# CCM_0020_receiver.net
KiCad netlist of a schematic drawn in EAGLE
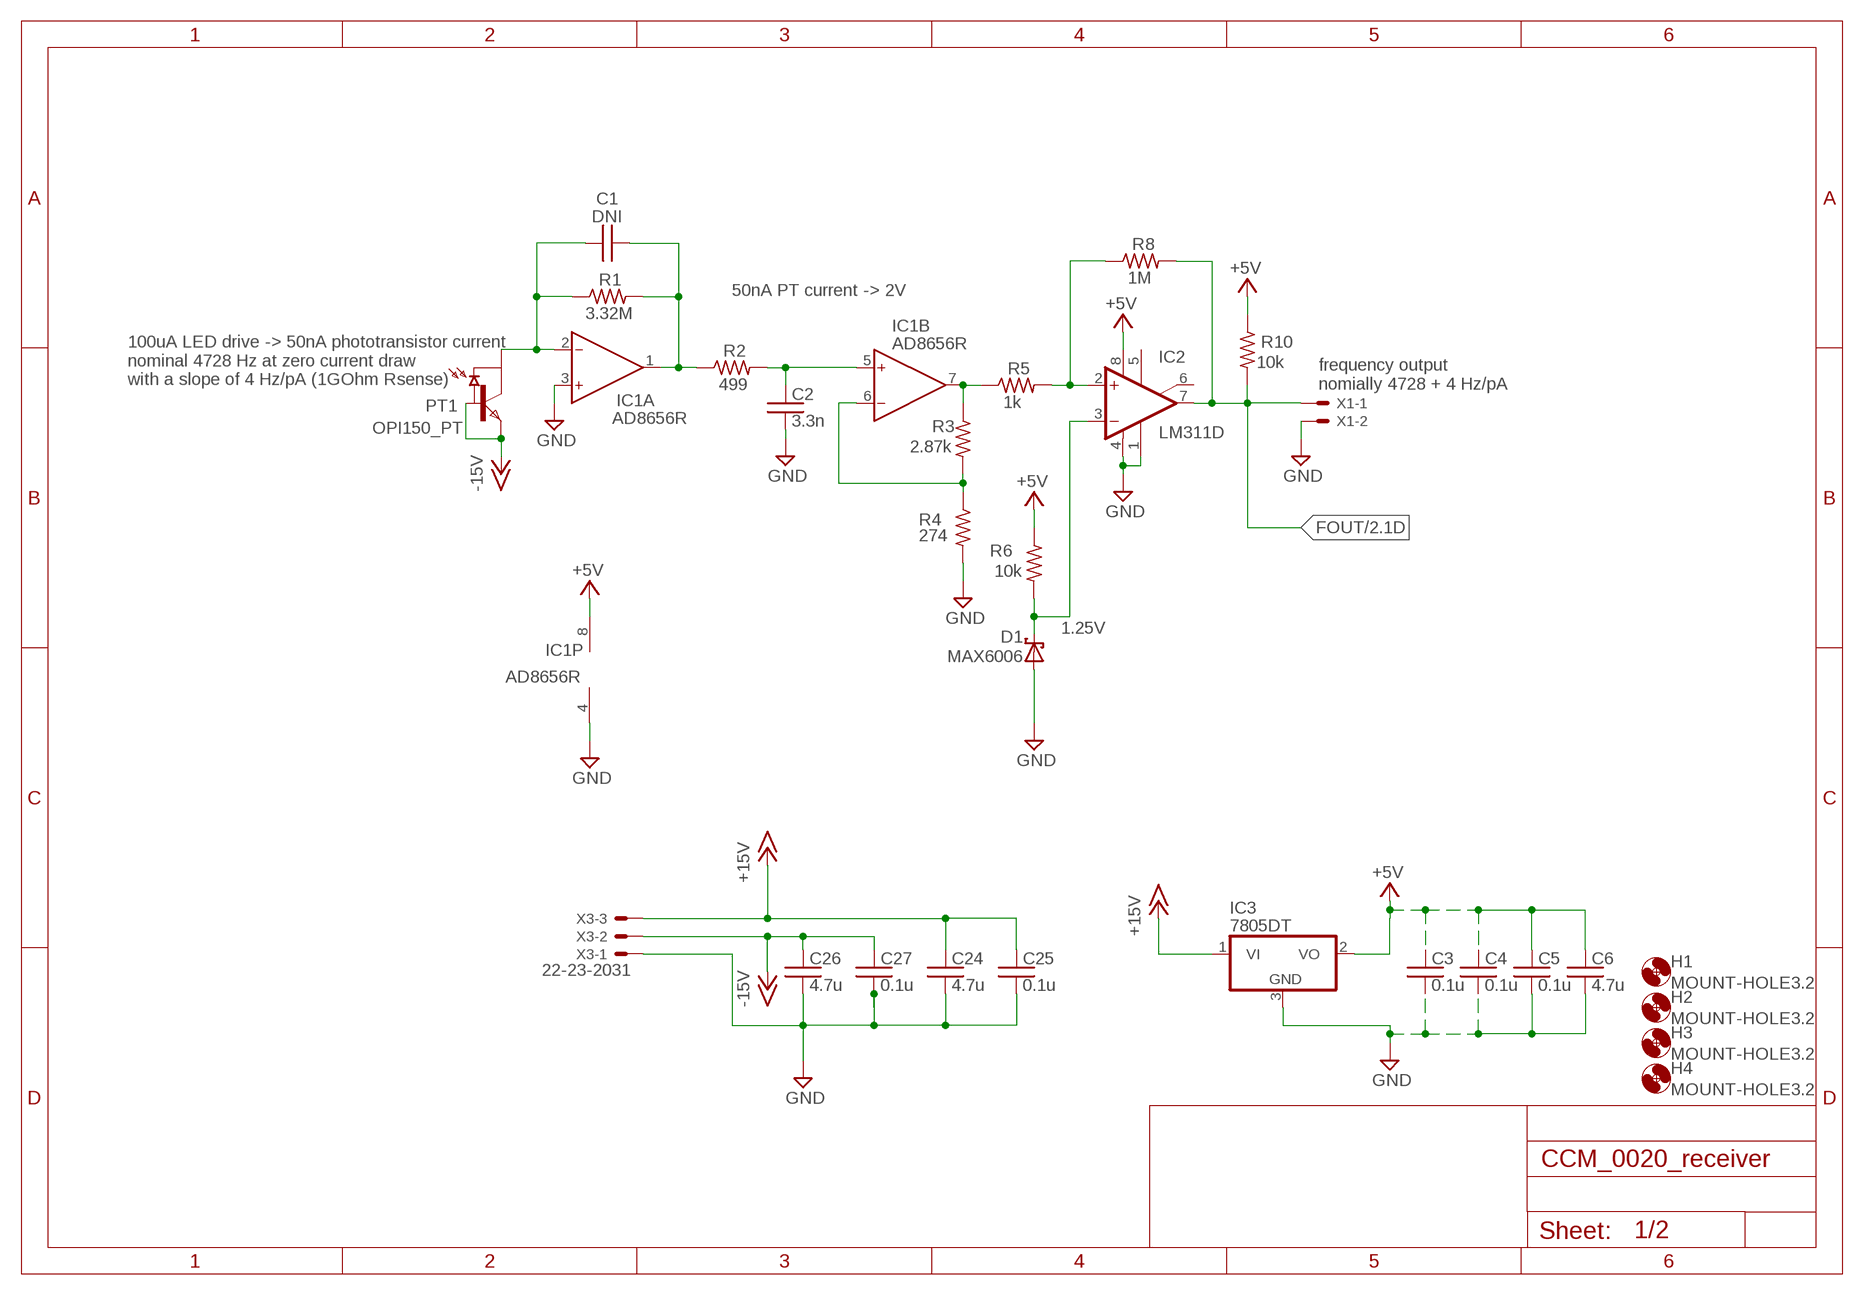
[diagram p0: schematic, sheet 1]
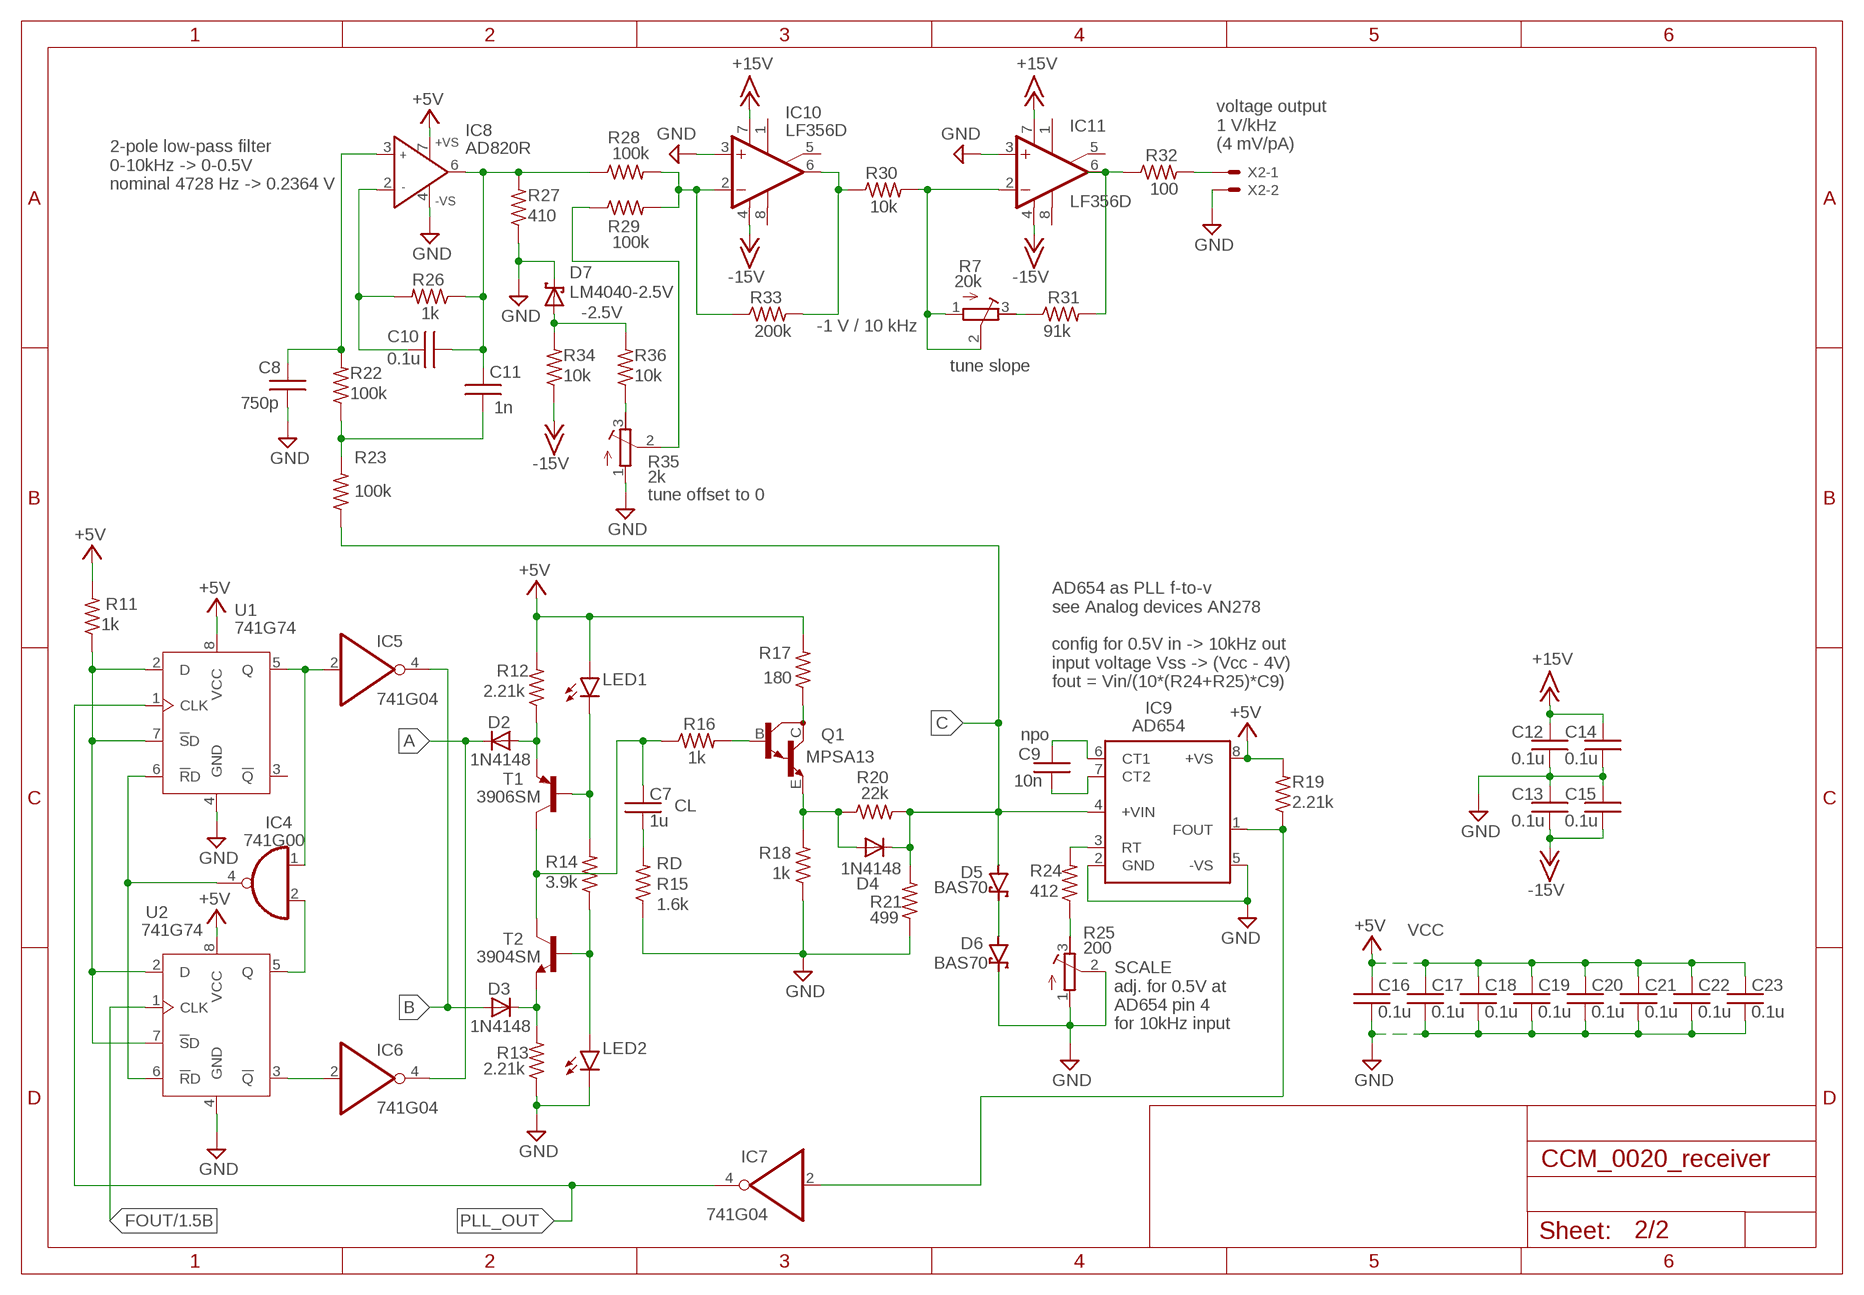
[diagram p1: schematic, sheet 2]

(export (version "E")
  (design (tool "Eeschema 10.0.6"))
  (components
    (comp (ref "C7")
      (value "1u")
      (footprint "eagle-import:0603")
      (libsource (lib "eagle-import") (part "C0603"))
    )
    (comp (ref "C8")
      (value "750p")
      (footprint "eagle-import:0603")
      (libsource (lib "eagle-import") (part "C0603"))
    )
    (comp (ref "C9")
      (value "10n")
      (footprint "eagle-import:0603")
      (libsource (lib "eagle-import") (part "C0603"))
    )
    (comp (ref "C10")
      (value "0.1u")
      (footprint "eagle-import:0603")
      (libsource (lib "eagle-import") (part "C0603"))
    )
    (comp (ref "C11")
      (value "1n")
      (footprint "eagle-import:0603")
      (libsource (lib "eagle-import") (part "C0603"))
    )
    (comp (ref "C12")
      (value "0.1u")
      (footprint "eagle-import:0603")
      (libsource (lib "eagle-import") (part "C0603"))
    )
    (comp (ref "C13")
      (value "0.1u")
      (footprint "eagle-import:0603")
      (libsource (lib "eagle-import") (part "C0603"))
    )
    (comp (ref "C14")
      (value "0.1u")
      (footprint "eagle-import:0603")
      (libsource (lib "eagle-import") (part "C0603"))
    )
    (comp (ref "C15")
      (value "0.1u")
      (footprint "eagle-import:0603")
      (libsource (lib "eagle-import") (part "C0603"))
    )
    (comp (ref "C16")
      (value "0.1u")
      (footprint "eagle-import:0603")
      (libsource (lib "eagle-import") (part "C0603"))
    )
    (comp (ref "C17")
      (value "0.1u")
      (footprint "eagle-import:0603")
      (libsource (lib "eagle-import") (part "C0603"))
    )
    (comp (ref "C18")
      (value "0.1u")
      (footprint "eagle-import:0603")
      (libsource (lib "eagle-import") (part "C0603"))
    )
    (comp (ref "C19")
      (value "0.1u")
      (footprint "eagle-import:0603")
      (libsource (lib "eagle-import") (part "C0603"))
    )
    (comp (ref "C20")
      (value "0.1u")
      (footprint "eagle-import:0603")
      (libsource (lib "eagle-import") (part "C0603"))
    )
    (comp (ref "C21")
      (value "0.1u")
      (footprint "eagle-import:0603")
      (libsource (lib "eagle-import") (part "C0603"))
    )
    (comp (ref "C22")
      (value "0.1u")
      (footprint "eagle-import:0603")
      (libsource (lib "eagle-import") (part "C0603"))
    )
    (comp (ref "C23")
      (value "0.1u")
      (footprint "eagle-import:0603")
      (libsource (lib "eagle-import") (part "C0603"))
    )
    (comp (ref "D2")
      (value "1N4148")
      (footprint "eagle-import:SOD323_ST")
      (libsource (lib "eagle-import") (part "1N4148"))
    )
    (comp (ref "D3")
      (value "1N4148")
      (footprint "eagle-import:SOD323_ST")
      (libsource (lib "eagle-import") (part "1N4148"))
    )
    (comp (ref "D4")
      (value "1N4148")
      (footprint "eagle-import:SOD323_ST")
      (libsource (lib "eagle-import") (part "1N4148"))
    )
    (comp (ref "D5")
      (value "BAS70")
      (footprint "eagle-import:SOT23")
      (libsource (lib "eagle-import") (part "BAS70"))
    )
    (comp (ref "D6")
      (value "BAS70")
      (footprint "eagle-import:SOT23")
      (libsource (lib "eagle-import") (part "BAS70"))
    )
    (comp (ref "D7")
      (value "LM4040-2.5V")
      (footprint "eagle-import:SOT23")
      (libsource (lib "eagle-import") (part "LM4040"))
    )
    (comp (ref "IC4")
      (value "741G00")
      (footprint "eagle-import:SOT23-5")
      (libsource (lib "eagle-import") (part "741G00DBVAHC"))
    )
    (comp (ref "IC5")
      (value "741G04")
      (footprint "eagle-import:SOT23-5")
      (libsource (lib "eagle-import") (part "741G04DBVAHC"))
    )
    (comp (ref "IC6")
      (value "741G04")
      (footprint "eagle-import:SOT23-5")
      (libsource (lib "eagle-import") (part "741G04DBVAHC"))
    )
    (comp (ref "IC7")
      (value "741G04")
      (footprint "eagle-import:SOT23-5")
      (libsource (lib "eagle-import") (part "741G04DBVAHC"))
    )
    (comp (ref "IC8")
      (value "AD820R")
      (footprint "eagle-import:SO8")
      (libsource (lib "eagle-import") (part "AD820R"))
    )
    (comp (ref "IC9")
      (value "AD654")
      (footprint "eagle-import:SO08")
      (libsource (lib "eagle-import") (part "AD654"))
    )
    (comp (ref "IC10")
      (value "LF356D")
      (footprint "eagle-import:SO08")
      (libsource (lib "eagle-import") (part "LF356D"))
    )
    (comp (ref "IC11")
      (value "LF356D")
      (footprint "eagle-import:SO08")
      (libsource (lib "eagle-import") (part "LF356D"))
    )
    (comp (ref "LED1")
      (value "LEDCHIP-LED0603")
      (footprint "eagle-import:CHIP-LED0603")
      (libsource (lib "eagle-import") (part "LEDCHIP-LED0603"))
    )
    (comp (ref "LED2")
      (value "LEDCHIP-LED0603")
      (footprint "eagle-import:CHIP-LED0603")
      (libsource (lib "eagle-import") (part "LEDCHIP-LED0603"))
    )
    (comp (ref "Q1")
      (value "MPSA13")
      (footprint "eagle-import:SOT23-BEC")
      (libsource (lib "eagle-import") (part "MMBTA13LT1"))
    )
    (comp (ref "R7")
      (value "20k")
      (footprint "eagle-import:RTRIM64Y")
      (libsource (lib "eagle-import") (part "R-TRIMM64Y"))
    )
    (comp (ref "R11")
      (value "1k")
      (footprint "eagle-import:0603")
      (libsource (lib "eagle-import") (part "R0603"))
    )
    (comp (ref "R12")
      (value "2.21k")
      (footprint "eagle-import:0603")
      (libsource (lib "eagle-import") (part "R0603"))
    )
    (comp (ref "R13")
      (value "2.21k")
      (footprint "eagle-import:0603")
      (libsource (lib "eagle-import") (part "R0603"))
    )
    (comp (ref "R14")
      (value "3.9k")
      (footprint "eagle-import:0603")
      (libsource (lib "eagle-import") (part "R0603"))
    )
    (comp (ref "R15")
      (value "1.6k")
      (footprint "eagle-import:0603")
      (libsource (lib "eagle-import") (part "R0603"))
    )
    (comp (ref "R16")
      (value "1k")
      (footprint "eagle-import:0603")
      (libsource (lib "eagle-import") (part "R0603"))
    )
    (comp (ref "R17")
      (value "180")
      (footprint "eagle-import:0603")
      (libsource (lib "eagle-import") (part "R0603"))
    )
    (comp (ref "R18")
      (value "1k")
      (footprint "eagle-import:0603")
      (libsource (lib "eagle-import") (part "R0603"))
    )
    (comp (ref "R19")
      (value "2.21k")
      (footprint "eagle-import:0603")
      (libsource (lib "eagle-import") (part "R0603"))
    )
    (comp (ref "R20")
      (value "22k")
      (footprint "eagle-import:0603")
      (libsource (lib "eagle-import") (part "R0603"))
    )
    (comp (ref "R21")
      (value "499")
      (footprint "eagle-import:0603")
      (libsource (lib "eagle-import") (part "R0603"))
    )
    (comp (ref "R22")
      (value "100k")
      (footprint "eagle-import:0603")
      (libsource (lib "eagle-import") (part "R0603"))
    )
    (comp (ref "R23")
      (value "100k")
      (footprint "eagle-import:0603")
      (libsource (lib "eagle-import") (part "R0603"))
    )
    (comp (ref "R24")
      (value "412")
      (footprint "eagle-import:0603")
      (libsource (lib "eagle-import") (part "R0603"))
    )
    (comp (ref "R25")
      (value "200")
      (footprint "eagle-import:RTRIM64Y")
      (libsource (lib "eagle-import") (part "R-TRIMM64Y"))
    )
    (comp (ref "R26")
      (value "1k")
      (footprint "eagle-import:0603")
      (libsource (lib "eagle-import") (part "R0603"))
    )
    (comp (ref "R27")
      (value "410")
      (footprint "eagle-import:0603")
      (libsource (lib "eagle-import") (part "R0603"))
    )
    (comp (ref "R28")
      (value "100k")
      (footprint "eagle-import:0603")
      (libsource (lib "eagle-import") (part "R0603"))
    )
    (comp (ref "R29")
      (value "100k")
      (footprint "eagle-import:0603")
      (libsource (lib "eagle-import") (part "R0603"))
    )
    (comp (ref "R30")
      (value "10k")
      (footprint "eagle-import:0603")
      (libsource (lib "eagle-import") (part "R0603"))
    )
    (comp (ref "R31")
      (value "91k")
      (footprint "eagle-import:0603")
      (libsource (lib "eagle-import") (part "R0603"))
    )
    (comp (ref "R32")
      (value "100")
      (footprint "eagle-import:0603")
      (libsource (lib "eagle-import") (part "R0603"))
    )
    (comp (ref "R33")
      (value "200k")
      (footprint "eagle-import:0603")
      (libsource (lib "eagle-import") (part "R0603"))
    )
    (comp (ref "R34")
      (value "10k")
      (footprint "eagle-import:0603")
      (libsource (lib "eagle-import") (part "R0603"))
    )
    (comp (ref "R35")
      (value "2k")
      (footprint "eagle-import:RTRIM64Y")
      (libsource (lib "eagle-import") (part "R-TRIMM64Y"))
    )
    (comp (ref "R36")
      (value "10k")
      (footprint "eagle-import:0603")
      (libsource (lib "eagle-import") (part "R0603"))
    )
    (comp (ref "T1")
      (value "3906SM")
      (footprint "eagle-import:SOT23-BEC")
      (libsource (lib "eagle-import") (part "-PNP-SOT23-BECMMBT3906LT1"))
    )
    (comp (ref "T2")
      (value "3904SM")
      (footprint "eagle-import:SOT23")
      (libsource (lib "eagle-import") (part "3904SM"))
    )
    (comp (ref "U1")
      (value "741G74")
      (footprint "eagle-import:TSSOP8")
      (libsource (lib "eagle-import") (part "741G74"))
    )
    (comp (ref "U2")
      (value "741G74")
      (footprint "eagle-import:TSSOP8")
      (libsource (lib "eagle-import") (part "741G74"))
    )
    (comp (ref "X2")
      (value "22-23-2021")
      (footprint "eagle-import:22-23-2021")
      (fields (field (name "MF") "MOLEX"))
      (libsource (lib "eagle-import") (part "22-23-2021"))
    )
    (comp (ref "C1")
      (value "DNI")
      (footprint "eagle-import:0603")
      (libsource (lib "eagle-import") (part "C0603"))
    )
    (comp (ref "C2")
      (value "3.3n")
      (footprint "eagle-import:0603")
      (libsource (lib "eagle-import") (part "C0603"))
    )
    (comp (ref "C3")
      (value "0.1u")
      (footprint "eagle-import:0603")
      (libsource (lib "eagle-import") (part "C0603"))
    )
    (comp (ref "C4")
      (value "0.1u")
      (footprint "eagle-import:0603")
      (libsource (lib "eagle-import") (part "C0603"))
    )
    (comp (ref "C5")
      (value "0.1u")
      (footprint "eagle-import:0603")
      (libsource (lib "eagle-import") (part "C0603"))
    )
    (comp (ref "C6")
      (value "4.7u")
      (footprint "eagle-import:0603")
      (libsource (lib "eagle-import") (part "C0603"))
    )
    (comp (ref "C24")
      (value "4.7u")
      (footprint "eagle-import:0603")
      (libsource (lib "eagle-import") (part "C0603"))
    )
    (comp (ref "C25")
      (value "0.1u")
      (footprint "eagle-import:0603")
      (libsource (lib "eagle-import") (part "C0603"))
    )
    (comp (ref "C26")
      (value "4.7u")
      (footprint "eagle-import:0603")
      (libsource (lib "eagle-import") (part "C0603"))
    )
    (comp (ref "C27")
      (value "0.1u")
      (footprint "eagle-import:0603")
      (libsource (lib "eagle-import") (part "C0603"))
    )
    (comp (ref "D1")
      (value "MAX6006")
      (footprint "eagle-import:SOT23")
      (libsource (lib "eagle-import") (part "LM4040"))
    )
    (comp (ref "H1")
      (value "MOUNT-HOLE3.2")
      (footprint "eagle-import:3,2")
      (libsource (lib "eagle-import") (part "MOUNT-HOLE3.2"))
    )
    (comp (ref "H2")
      (value "MOUNT-HOLE3.2")
      (footprint "eagle-import:3,2")
      (libsource (lib "eagle-import") (part "MOUNT-HOLE3.2"))
    )
    (comp (ref "H3")
      (value "MOUNT-HOLE3.2")
      (footprint "eagle-import:3,2")
      (libsource (lib "eagle-import") (part "MOUNT-HOLE3.2"))
    )
    (comp (ref "H4")
      (value "MOUNT-HOLE3.2")
      (footprint "eagle-import:3,2")
      (libsource (lib "eagle-import") (part "MOUNT-HOLE3.2"))
    )
    (comp (ref "IC1")
      (value "AD8656R")
      (footprint "eagle-import:SO8")
      (fields (field (name "MPN") "AD8656ARZ"))
      (libsource (lib "eagle-import") (part "AD8656R"))
    )
    (comp (ref "IC2")
      (value "LM311D")
      (footprint "eagle-import:SO08")
      (libsource (lib "eagle-import") (part "LM311D"))
    )
    (comp (ref "IC3")
      (value "7805DT")
      (footprint "eagle-import:TO252")
      (libsource (lib "eagle-import") (part "78DT05"))
    )
    (comp (ref "PT1")
      (value "OPI150_PT")
      (footprint "eagle-import:OPI150_PHOTOTRANSISTOR")
      (libsource (lib "eagle-import") (part "OPI150_PHOTOTRANSISTOR"))
    )
    (comp (ref "R1")
      (value "3.32M")
      (footprint "eagle-import:0603")
      (libsource (lib "eagle-import") (part "R0603"))
    )
    (comp (ref "R2")
      (value "499")
      (footprint "eagle-import:0603")
      (libsource (lib "eagle-import") (part "R0603"))
    )
    (comp (ref "R3")
      (value "2.87k")
      (footprint "eagle-import:0603")
      (libsource (lib "eagle-import") (part "R0603"))
    )
    (comp (ref "R4")
      (value "274")
      (footprint "eagle-import:0603")
      (libsource (lib "eagle-import") (part "R0603"))
    )
    (comp (ref "R5")
      (value "1k")
      (footprint "eagle-import:0603")
      (libsource (lib "eagle-import") (part "R0603"))
    )
    (comp (ref "R6")
      (value "10k")
      (footprint "eagle-import:0603")
      (libsource (lib "eagle-import") (part "R0603"))
    )
    (comp (ref "R8")
      (value "1M")
      (footprint "eagle-import:0603")
      (libsource (lib "eagle-import") (part "R0603"))
    )
    (comp (ref "R10")
      (value "10k")
      (footprint "eagle-import:0603")
      (libsource (lib "eagle-import") (part "R0603"))
    )
    (comp (ref "X1")
      (value "22-23-2021")
      (footprint "eagle-import:22-23-2021")
      (fields (field (name "MF") "MOLEX"))
      (libsource (lib "eagle-import") (part "22-23-2021"))
    )
    (comp (ref "X3")
      (value "22-23-2031")
      (footprint "eagle-import:22-23-2031")
      (fields (field (name "MF") "MOLEX"))
      (libsource (lib "eagle-import") (part "22-23-2031"))
    )
  )
  (nets
    (net (code "1") (name "+15V") (class "Default")
      (node (ref "C12") (pin "2") (pinfunction "2_2") (pintype "passive"))
      (node (ref "C14") (pin "2") (pinfunction "2_2") (pintype "passive"))
      (node (ref "C24") (pin "1") (pinfunction "1_1") (pintype "passive"))
      (node (ref "C25") (pin "1") (pinfunction "1_1") (pintype "passive"))
      (node (ref "IC10") (pin "7") (pinfunction "V+_7") (pintype "power_in"))
      (node (ref "IC11") (pin "7") (pinfunction "V+_7") (pintype "power_in"))
      (node (ref "IC3") (pin "1") (pinfunction "VI_1") (pintype "input"))
      (node (ref "X3") (pin "3") (pinfunction "S_3") (pintype "passive"))
    )
    (net (code "2") (name "-15V") (class "Default")
      (node (ref "C13") (pin "1") (pinfunction "1_1") (pintype "passive"))
      (node (ref "C15") (pin "1") (pinfunction "1_1") (pintype "passive"))
      (node (ref "C26") (pin "1") (pinfunction "1_1") (pintype "passive"))
      (node (ref "C27") (pin "1") (pinfunction "1_1") (pintype "passive"))
      (node (ref "IC10") (pin "4") (pinfunction "V-_4") (pintype "power_in"))
      (node (ref "IC11") (pin "4") (pinfunction "V-_4") (pintype "power_in"))
      (node (ref "PT1") (pin "P4") (pinfunction "BASE_P4") (pintype "passive"))
      (node (ref "PT1") (pin "P5") (pinfunction "EMITTER_P5") (pintype "passive"))
      (node (ref "R34") (pin "1") (pinfunction "1_1") (pintype "passive"))
      (node (ref "X3") (pin "2") (pinfunction "S_2") (pintype "passive"))
    )
    (net (code "3") (name "A") (class "Default")
      (node (ref "D2") (pin "C") (pinfunction "C_C") (pintype "passive"))
      (node (ref "IC6") (pin "4") (pinfunction "O_4") (pintype "output"))
    )
    (net (code "4") (name "B") (class "Default")
      (node (ref "D3") (pin "A") (pinfunction "A_A") (pintype "passive"))
      (node (ref "IC5") (pin "4") (pinfunction "O_4") (pintype "output"))
    )
    (net (code "5") (name "C") (class "Default")
      (node (ref "D4") (pin "C") (pinfunction "C_C") (pintype "passive"))
      (node (ref "D5") (pin "1") (pinfunction "A_1") (pintype "passive"))
      (node (ref "IC9") (pin "4") (pinfunction "+VIN_4") (pintype "input"))
      (node (ref "R20") (pin "2") (pinfunction "2_2") (pintype "passive"))
      (node (ref "R21") (pin "2") (pinfunction "2_2") (pintype "passive"))
      (node (ref "R23") (pin "1") (pinfunction "1_1") (pintype "passive"))
    )
    (net (code "6") (name "FOUT") (class "Default")
      (node (ref "IC2") (pin "7") (pinfunction "OUT_7") (pintype "output"))
      (node (ref "R10") (pin "2") (pinfunction "2_2") (pintype "passive"))
      (node (ref "R8") (pin "2") (pinfunction "2_2") (pintype "passive"))
      (node (ref "U2") (pin "1") (pinfunction "CLK_1") (pintype "bidirectional"))
      (node (ref "X1") (pin "1") (pinfunction "S_1") (pintype "passive"))
    )
    (net (code "7") (name "GND") (class "Default")
      (node (ref "C12") (pin "1") (pinfunction "1_1") (pintype "passive"))
      (node (ref "C13") (pin "2") (pinfunction "2_2") (pintype "passive"))
      (node (ref "C14") (pin "1") (pinfunction "1_1") (pintype "passive"))
      (node (ref "C15") (pin "2") (pinfunction "2_2") (pintype "passive"))
      (node (ref "C16") (pin "2") (pinfunction "2_2") (pintype "passive"))
      (node (ref "C17") (pin "2") (pinfunction "2_2") (pintype "passive"))
      (node (ref "C18") (pin "2") (pinfunction "2_2") (pintype "passive"))
      (node (ref "C19") (pin "2") (pinfunction "2_2") (pintype "passive"))
      (node (ref "C2") (pin "2") (pinfunction "2_2") (pintype "passive"))
      (node (ref "C20") (pin "2") (pinfunction "2_2") (pintype "passive"))
      (node (ref "C21") (pin "2") (pinfunction "2_2") (pintype "passive"))
      (node (ref "C22") (pin "2") (pinfunction "2_2") (pintype "passive"))
      (node (ref "C23") (pin "2") (pinfunction "2_2") (pintype "passive"))
      (node (ref "C24") (pin "2") (pinfunction "2_2") (pintype "passive"))
      (node (ref "C25") (pin "2") (pinfunction "2_2") (pintype "passive"))
      (node (ref "C26") (pin "2") (pinfunction "2_2") (pintype "passive"))
      (node (ref "C27") (pin "2") (pinfunction "2_2") (pintype "passive"))
      (node (ref "C3") (pin "2") (pinfunction "2_2") (pintype "passive"))
      (node (ref "C4") (pin "2") (pinfunction "2_2") (pintype "passive"))
      (node (ref "C5") (pin "2") (pinfunction "2_2") (pintype "passive"))
      (node (ref "C6") (pin "2") (pinfunction "2_2") (pintype "passive"))
      (node (ref "C8") (pin "1") (pinfunction "1_1") (pintype "passive"))
      (node (ref "D1") (pin "2") (pinfunction "A_2") (pintype "passive"))
      (node (ref "D6") (pin "3") (pinfunction "C_3") (pintype "passive"))
      (node (ref "D7") (pin "1") (pinfunction "C_1") (pintype "passive"))
      (node (ref "IC1") (pin "3") (pinfunction "IN+_3") (pintype "input"))
      (node (ref "IC1") (pin "4") (pinfunction "V-_4") (pintype "power_in"))
      (node (ref "IC10") (pin "3") (pinfunction "+IN_3") (pintype "input"))
      (node (ref "IC11") (pin "3") (pinfunction "+IN_3") (pintype "input"))
      (node (ref "IC2") (pin "1") (pinfunction "GND_1") (pintype "passive"))
      (node (ref "IC2") (pin "4") (pinfunction "V-_4") (pintype "power_in"))
      (node (ref "IC3") (pin "3") (pinfunction "GND_3") (pintype "passive"))
      (node (ref "IC8") (pin "4") (pinfunction "-VS_4") (pintype "input"))
      (node (ref "IC9") (pin "2") (pinfunction "GND_2") (pintype "power_in"))
      (node (ref "IC9") (pin "5") (pinfunction "-VS_5") (pintype "power_in"))
      (node (ref "LED2") (pin "C") (pinfunction "C_C") (pintype "passive"))
      (node (ref "R13") (pin "1") (pinfunction "1_1") (pintype "passive"))
      (node (ref "R15") (pin "1") (pinfunction "1_1") (pintype "passive"))
      (node (ref "R18") (pin "1") (pinfunction "1_1") (pintype "passive"))
      (node (ref "R21") (pin "1") (pinfunction "1_1") (pintype "passive"))
      (node (ref "R25") (pin "1") (pinfunction "A_1") (pintype "passive"))
      (node (ref "R25") (pin "2") (pinfunction "S_2") (pintype "passive"))
      (node (ref "R27") (pin "1") (pinfunction "1_1") (pintype "passive"))
      (node (ref "R35") (pin "1") (pinfunction "A_1") (pintype "passive"))
      (node (ref "R4") (pin "2") (pinfunction "2_2") (pintype "passive"))
      (node (ref "U1") (pin "4") (pinfunction "GND_4") (pintype "bidirectional"))
      (node (ref "U2") (pin "4") (pinfunction "GND_4") (pintype "bidirectional"))
      (node (ref "X1") (pin "2") (pinfunction "S_2") (pintype "passive"))
      (node (ref "X2") (pin "2") (pinfunction "S_2") (pintype "passive"))
      (node (ref "X3") (pin "1") (pinfunction "S_1") (pintype "passive"))
    )
    (net (code "8") (name "Net-(C7-Pad2)") (class "Default")
      (node (ref "C7") (pin "2") (pinfunction "2_2") (pintype "passive"))
      (node (ref "R15") (pin "2") (pinfunction "2_2") (pintype "passive"))
    )
    (net (code "9") (name "Net-(C11-Pad1)") (class "Default")
      (node (ref "C11") (pin "1") (pinfunction "1_1") (pintype "passive"))
      (node (ref "R22") (pin "1") (pinfunction "1_1") (pintype "passive"))
      (node (ref "R23") (pin "2") (pinfunction "2_2") (pintype "passive"))
    )
    (net (code "10") (name "Net-(D1-C)") (class "Default")
      (node (ref "D1") (pin "1") (pinfunction "C_1") (pintype "passive"))
      (node (ref "IC2") (pin "3") (pinfunction "-IN_3") (pintype "input"))
      (node (ref "R6") (pin "2") (pinfunction "2_2") (pintype "passive"))
    )
    (net (code "11") (name "Net-(D2-PadA)") (class "Default")
      (node (ref "D2") (pin "A") (pinfunction "A_A") (pintype "passive"))
      (node (ref "R12") (pin "1") (pinfunction "1_1") (pintype "passive"))
      (node (ref "T1") (pin "E") (pinfunction "E_E") (pintype "passive"))
    )
    (net (code "12") (name "Net-(D4-PadA)") (class "Default")
      (node (ref "D4") (pin "A") (pinfunction "A_A") (pintype "passive"))
      (node (ref "Q1") (pin "E") (pinfunction "E_E") (pintype "passive"))
      (node (ref "R18") (pin "2") (pinfunction "2_2") (pintype "passive"))
      (node (ref "R20") (pin "1") (pinfunction "1_1") (pintype "passive"))
    )
    (net (code "13") (name "Net-(D5-C)") (class "Default")
      (node (ref "D5") (pin "3") (pinfunction "C_3") (pintype "passive"))
      (node (ref "D6") (pin "1") (pinfunction "A_1") (pintype "passive"))
    )
    (net (code "14") (name "Net-(D7-A)") (class "Default")
      (node (ref "D7") (pin "2") (pinfunction "A_2") (pintype "passive"))
      (node (ref "R34") (pin "2") (pinfunction "2_2") (pintype "passive"))
      (node (ref "R36") (pin "2") (pinfunction "2_2") (pintype "passive"))
    )
    (net (code "15") (name "Net-(IC1A-IN-)") (class "Default")
      (node (ref "C1") (pin "1") (pinfunction "1_1") (pintype "passive"))
      (node (ref "IC1") (pin "2") (pinfunction "IN-_2") (pintype "input"))
      (node (ref "PT1") (pin "P3") (pinfunction "COLLECTOR_P3") (pintype "passive"))
      (node (ref "R1") (pin "1") (pinfunction "1_1") (pintype "passive"))
    )
    (net (code "16") (name "Net-(IC1A-OUT)") (class "Default")
      (node (ref "C1") (pin "2") (pinfunction "2_2") (pintype "passive"))
      (node (ref "IC1") (pin "1") (pinfunction "OUT_1") (pintype "output"))
      (node (ref "R1") (pin "2") (pinfunction "2_2") (pintype "passive"))
      (node (ref "R2") (pin "1") (pinfunction "1_1") (pintype "passive"))
    )
    (net (code "17") (name "Net-(IC1B-IN+)") (class "Default")
      (node (ref "C2") (pin "1") (pinfunction "1_1") (pintype "passive"))
      (node (ref "IC1") (pin "5") (pinfunction "IN+_5") (pintype "input"))
      (node (ref "R2") (pin "2") (pinfunction "2_2") (pintype "passive"))
    )
    (net (code "18") (name "Net-(IC1B-IN-)") (class "Default")
      (node (ref "IC1") (pin "6") (pinfunction "IN-_6") (pintype "input"))
      (node (ref "R3") (pin "2") (pinfunction "2_2") (pintype "passive"))
      (node (ref "R4") (pin "1") (pinfunction "1_1") (pintype "passive"))
    )
    (net (code "19") (name "Net-(IC1B-OUT)") (class "Default")
      (node (ref "IC1") (pin "7") (pinfunction "OUT_7") (pintype "output"))
      (node (ref "R3") (pin "1") (pinfunction "1_1") (pintype "passive"))
      (node (ref "R5") (pin "1") (pinfunction "1_1") (pintype "passive"))
    )
    (net (code "20") (name "Net-(IC2-+IN)") (class "Default")
      (node (ref "IC2") (pin "2") (pinfunction "+IN_2") (pintype "input"))
      (node (ref "R5") (pin "2") (pinfunction "2_2") (pintype "passive"))
      (node (ref "R8") (pin "1") (pinfunction "1_1") (pintype "passive"))
    )
    (net (code "21") (name "Net-(IC4A-I0)") (class "Default")
      (node (ref "IC4") (pin "1") (pinfunction "I0_1") (pintype "input"))
      (node (ref "IC5") (pin "2") (pinfunction "I_2") (pintype "input"))
      (node (ref "U1") (pin "5") (pinfunction "Q_5") (pintype "bidirectional"))
    )
    (net (code "22") (name "Net-(IC4A-I1)") (class "Default")
      (node (ref "IC4") (pin "2") (pinfunction "I1_2") (pintype "input"))
      (node (ref "U2") (pin "5") (pinfunction "Q_5") (pintype "bidirectional"))
    )
    (net (code "23") (name "Net-(IC4A-O)") (class "Default")
      (node (ref "IC4") (pin "4") (pinfunction "O_4") (pintype "output"))
      (node (ref "U1") (pin "6") (pinfunction "~{R}D_6") (pintype "bidirectional"))
      (node (ref "U2") (pin "6") (pinfunction "~{R}D_6") (pintype "bidirectional"))
    )
    (net (code "24") (name "Net-(IC6A-I)") (class "Default")
      (node (ref "IC6") (pin "2") (pinfunction "I_2") (pintype "input"))
      (node (ref "U2") (pin "3") (pinfunction "~{Q}_3") (pintype "bidirectional"))
    )
    (net (code "25") (name "Net-(IC7A-I)") (class "Default")
      (node (ref "IC7") (pin "2") (pinfunction "I_2") (pintype "input"))
      (node (ref "IC9") (pin "1") (pinfunction "FOUT_1") (pintype "open_collector"))
      (node (ref "R19") (pin "1") (pinfunction "1_1") (pintype "passive"))
    )
    (net (code "26") (name "Net-(IC8-IN+)") (class "Default")
      (node (ref "C8") (pin "2") (pinfunction "2_2") (pintype "passive"))
      (node (ref "IC8") (pin "3") (pinfunction "IN+_3") (pintype "input"))
      (node (ref "R22") (pin "2") (pinfunction "2_2") (pintype "passive"))
    )
    (net (code "27") (name "Net-(IC8-IN-)") (class "Default")
      (node (ref "C10") (pin "1") (pinfunction "1_1") (pintype "passive"))
      (node (ref "IC8") (pin "2") (pinfunction "IN-_2") (pintype "input"))
      (node (ref "R26") (pin "2") (pinfunction "2_2") (pintype "passive"))
    )
    (net (code "28") (name "Net-(IC8-OUT)") (class "Default")
      (node (ref "C10") (pin "2") (pinfunction "2_2") (pintype "passive"))
      (node (ref "C11") (pin "2") (pinfunction "2_2") (pintype "passive"))
      (node (ref "IC8") (pin "6") (pinfunction "OUT_6") (pintype "output"))
      (node (ref "R26") (pin "1") (pinfunction "1_1") (pintype "passive"))
      (node (ref "R27") (pin "2") (pinfunction "2_2") (pintype "passive"))
      (node (ref "R28") (pin "1") (pinfunction "1_1") (pintype "passive"))
    )
    (net (code "29") (name "Net-(IC9-CT1)") (class "Default")
      (node (ref "C9") (pin "1") (pinfunction "1_1") (pintype "passive"))
      (node (ref "IC9") (pin "6") (pinfunction "CT1_6") (pintype "passive"))
    )
    (net (code "30") (name "Net-(IC9-CT2)") (class "Default")
      (node (ref "C9") (pin "2") (pinfunction "2_2") (pintype "passive"))
      (node (ref "IC9") (pin "7") (pinfunction "CT2_7") (pintype "passive"))
    )
    (net (code "31") (name "Net-(IC9-RT)") (class "Default")
      (node (ref "IC9") (pin "3") (pinfunction "RT_3") (pintype "passive"))
      (node (ref "R24") (pin "2") (pinfunction "2_2") (pintype "passive"))
    )
    (net (code "32") (name "Net-(IC10--IN)") (class "Default")
      (node (ref "IC10") (pin "2") (pinfunction "-IN_2") (pintype "input"))
      (node (ref "R28") (pin "2") (pinfunction "2_2") (pintype "passive"))
      (node (ref "R29") (pin "2") (pinfunction "2_2") (pintype "passive"))
      (node (ref "R33") (pin "1") (pinfunction "1_1") (pintype "passive"))
    )
    (net (code "33") (name "Net-(IC10-OUT)") (class "Default")
      (node (ref "IC10") (pin "6") (pinfunction "OUT_6") (pintype "output"))
      (node (ref "R30") (pin "1") (pinfunction "1_1") (pintype "passive"))
      (node (ref "R33") (pin "2") (pinfunction "2_2") (pintype "passive"))
    )
    (net (code "34") (name "Net-(IC11--IN)") (class "Default")
      (node (ref "IC11") (pin "2") (pinfunction "-IN_2") (pintype "input"))
      (node (ref "R30") (pin "2") (pinfunction "2_2") (pintype "passive"))
      (node (ref "R7") (pin "1") (pinfunction "A_1") (pintype "passive"))
      (node (ref "R7") (pin "2") (pinfunction "S_2") (pintype "passive"))
    )
    (net (code "35") (name "Net-(IC11-OUT)") (class "Default")
      (node (ref "IC11") (pin "6") (pinfunction "OUT_6") (pintype "output"))
      (node (ref "R31") (pin "2") (pinfunction "2_2") (pintype "passive"))
      (node (ref "R32") (pin "1") (pinfunction "1_1") (pintype "passive"))
    )
    (net (code "36") (name "Net-(LED1-PadC)") (class "Default")
      (node (ref "LED1") (pin "C") (pinfunction "C_C") (pintype "passive"))
      (node (ref "R14") (pin "2") (pinfunction "2_2") (pintype "passive"))
      (node (ref "T1") (pin "B") (pinfunction "B_B") (pintype "passive"))
    )
    (net (code "37") (name "Net-(Q1-PadB)") (class "Default")
      (node (ref "Q1") (pin "B") (pinfunction "B_B") (pintype "passive"))
      (node (ref "R16") (pin "2") (pinfunction "2_2") (pintype "passive"))
    )
    (net (code "38") (name "Net-(Q1-PadC)") (class "Default")
      (node (ref "Q1") (pin "C") (pinfunction "C_C") (pintype "passive"))
      (node (ref "R17") (pin "1") (pinfunction "1_1") (pintype "passive"))
    )
    (net (code "39") (name "Net-(R7-E)") (class "Default")
      (node (ref "R31") (pin "1") (pinfunction "1_1") (pintype "passive"))
      (node (ref "R7") (pin "3") (pinfunction "E_3") (pintype "passive"))
    )
    (net (code "40") (name "Net-(R25-E)") (class "Default")
      (node (ref "R24") (pin "1") (pinfunction "1_1") (pintype "passive"))
      (node (ref "R25") (pin "3") (pinfunction "E_3") (pintype "passive"))
    )
    (net (code "41") (name "Net-(R35-E)") (class "Default")
      (node (ref "R35") (pin "3") (pinfunction "E_3") (pintype "passive"))
      (node (ref "R36") (pin "1") (pinfunction "1_1") (pintype "passive"))
    )
    (net (code "42") (name "Net-(R35-S)") (class "Default")
      (node (ref "R29") (pin "1") (pinfunction "1_1") (pintype "passive"))
      (node (ref "R35") (pin "2") (pinfunction "S_2") (pintype "passive"))
    )
    (net (code "43") (name "Net-(T2-B)") (class "Default")
      (node (ref "LED2") (pin "A") (pinfunction "A_A") (pintype "passive"))
      (node (ref "R14") (pin "1") (pinfunction "1_1") (pintype "passive"))
      (node (ref "T2") (pin "1") (pinfunction "B_1") (pintype "passive"))
    )
    (net (code "44") (name "Net-(T2-C)") (class "Default")
      (node (ref "C7") (pin "1") (pinfunction "1_1") (pintype "passive"))
      (node (ref "R16") (pin "1") (pinfunction "1_1") (pintype "passive"))
      (node (ref "T1") (pin "C") (pinfunction "C_C") (pintype "passive"))
      (node (ref "T2") (pin "3") (pinfunction "C_3") (pintype "passive"))
    )
    (net (code "45") (name "Net-(T2-E)") (class "Default")
      (node (ref "D3") (pin "C") (pinfunction "C_C") (pintype "passive"))
      (node (ref "R13") (pin "2") (pinfunction "2_2") (pintype "passive"))
      (node (ref "T2") (pin "2") (pinfunction "E_2") (pintype "passive"))
    )
    (net (code "46") (name "Net-(U1-D)") (class "Default")
      (node (ref "R11") (pin "1") (pinfunction "1_1") (pintype "passive"))
      (node (ref "U1") (pin "2") (pinfunction "D_2") (pintype "bidirectional"))
      (node (ref "U1") (pin "7") (pinfunction "~{S}D_7") (pintype "bidirectional"))
      (node (ref "U2") (pin "2") (pinfunction "D_2") (pintype "bidirectional"))
      (node (ref "U2") (pin "7") (pinfunction "~{S}D_7") (pintype "bidirectional"))
    )
    (net (code "47") (name "Net-(X2A-S)") (class "Default")
      (node (ref "R32") (pin "2") (pinfunction "2_2") (pintype "passive"))
      (node (ref "X2") (pin "1") (pinfunction "S_1") (pintype "passive"))
    )
    (net (code "48") (name "PLL_OUT") (class "Default")
      (node (ref "IC7") (pin "4") (pinfunction "O_4") (pintype "output"))
      (node (ref "U1") (pin "1") (pinfunction "CLK_1") (pintype "bidirectional"))
    )
    (net (code "49") (name "VCC") (class "Default")
      (node (ref "C16") (pin "1") (pinfunction "1_1") (pintype "passive"))
      (node (ref "C17") (pin "1") (pinfunction "1_1") (pintype "passive"))
      (node (ref "C18") (pin "1") (pinfunction "1_1") (pintype "passive"))
      (node (ref "C19") (pin "1") (pinfunction "1_1") (pintype "passive"))
      (node (ref "C20") (pin "1") (pinfunction "1_1") (pintype "passive"))
      (node (ref "C21") (pin "1") (pinfunction "1_1") (pintype "passive"))
      (node (ref "C22") (pin "1") (pinfunction "1_1") (pintype "passive"))
      (node (ref "C23") (pin "1") (pinfunction "1_1") (pintype "passive"))
      (node (ref "C3") (pin "1") (pinfunction "1_1") (pintype "passive"))
      (node (ref "C4") (pin "1") (pinfunction "1_1") (pintype "passive"))
      (node (ref "C5") (pin "1") (pinfunction "1_1") (pintype "passive"))
      (node (ref "C6") (pin "1") (pinfunction "1_1") (pintype "passive"))
      (node (ref "IC1") (pin "8") (pinfunction "V+_8") (pintype "power_in"))
      (node (ref "IC2") (pin "8") (pinfunction "V+_8") (pintype "power_in"))
      (node (ref "IC3") (pin "2") (pinfunction "VO_2") (pintype "passive"))
      (node (ref "IC8") (pin "7") (pinfunction "+VS_7") (pintype "input"))
      (node (ref "IC9") (pin "8") (pinfunction "+VS_8") (pintype "power_in"))
      (node (ref "LED1") (pin "A") (pinfunction "A_A") (pintype "passive"))
      (node (ref "R10") (pin "1") (pinfunction "1_1") (pintype "passive"))
      (node (ref "R11") (pin "2") (pinfunction "2_2") (pintype "passive"))
      (node (ref "R12") (pin "2") (pinfunction "2_2") (pintype "passive"))
      (node (ref "R17") (pin "2") (pinfunction "2_2") (pintype "passive"))
      (node (ref "R19") (pin "2") (pinfunction "2_2") (pintype "passive"))
      (node (ref "R6") (pin "1") (pinfunction "1_1") (pintype "passive"))
      (node (ref "U1") (pin "8") (pinfunction "VCC_8") (pintype "bidirectional"))
      (node (ref "U2") (pin "8") (pinfunction "VCC_8") (pintype "bidirectional"))
    )
    (net (code "50") (name "unconnected-(IC2-ON-Pad5)") (class "Default")
      (node (ref "IC2") (pin "5") (pinfunction "ON_5") (pintype "passive"))
    )
    (net (code "51") (name "unconnected-(IC2-ON{slash}STR-Pad6)") (class "Default")
      (node (ref "IC2") (pin "6") (pinfunction "ON/STR_6") (pintype "passive"))
    )
    (net (code "52") (name "unconnected-(IC10-ON1-Pad1)") (class "Default")
      (node (ref "IC10") (pin "1") (pinfunction "ON1_1") (pintype "passive"))
    )
    (net (code "53") (name "unconnected-(IC10-ON2-Pad5)") (class "Default")
      (node (ref "IC10") (pin "5") (pinfunction "ON2_5") (pintype "passive"))
    )
    (net (code "54") (name "unconnected-(IC10-OPT-Pad8)") (class "Default")
      (node (ref "IC10") (pin "8") (pinfunction "OPT_8") (pintype "passive"))
    )
    (net (code "55") (name "unconnected-(IC11-ON1-Pad1)") (class "Default")
      (node (ref "IC11") (pin "1") (pinfunction "ON1_1") (pintype "passive"))
    )
    (net (code "56") (name "unconnected-(IC11-ON2-Pad5)") (class "Default")
      (node (ref "IC11") (pin "5") (pinfunction "ON2_5") (pintype "passive"))
    )
    (net (code "57") (name "unconnected-(IC11-OPT-Pad8)") (class "Default")
      (node (ref "IC11") (pin "8") (pinfunction "OPT_8") (pintype "passive"))
    )
    (net (code "58") (name "unconnected-(U1-~{Q}-Pad3)") (class "Default")
      (node (ref "U1") (pin "3") (pinfunction "~{Q}_3") (pintype "bidirectional"))
    )
  )
)
